# SCH_ZX-WiFi_2024-06-03.net
KiCad netlist of a schematic drawn in EasyEDA
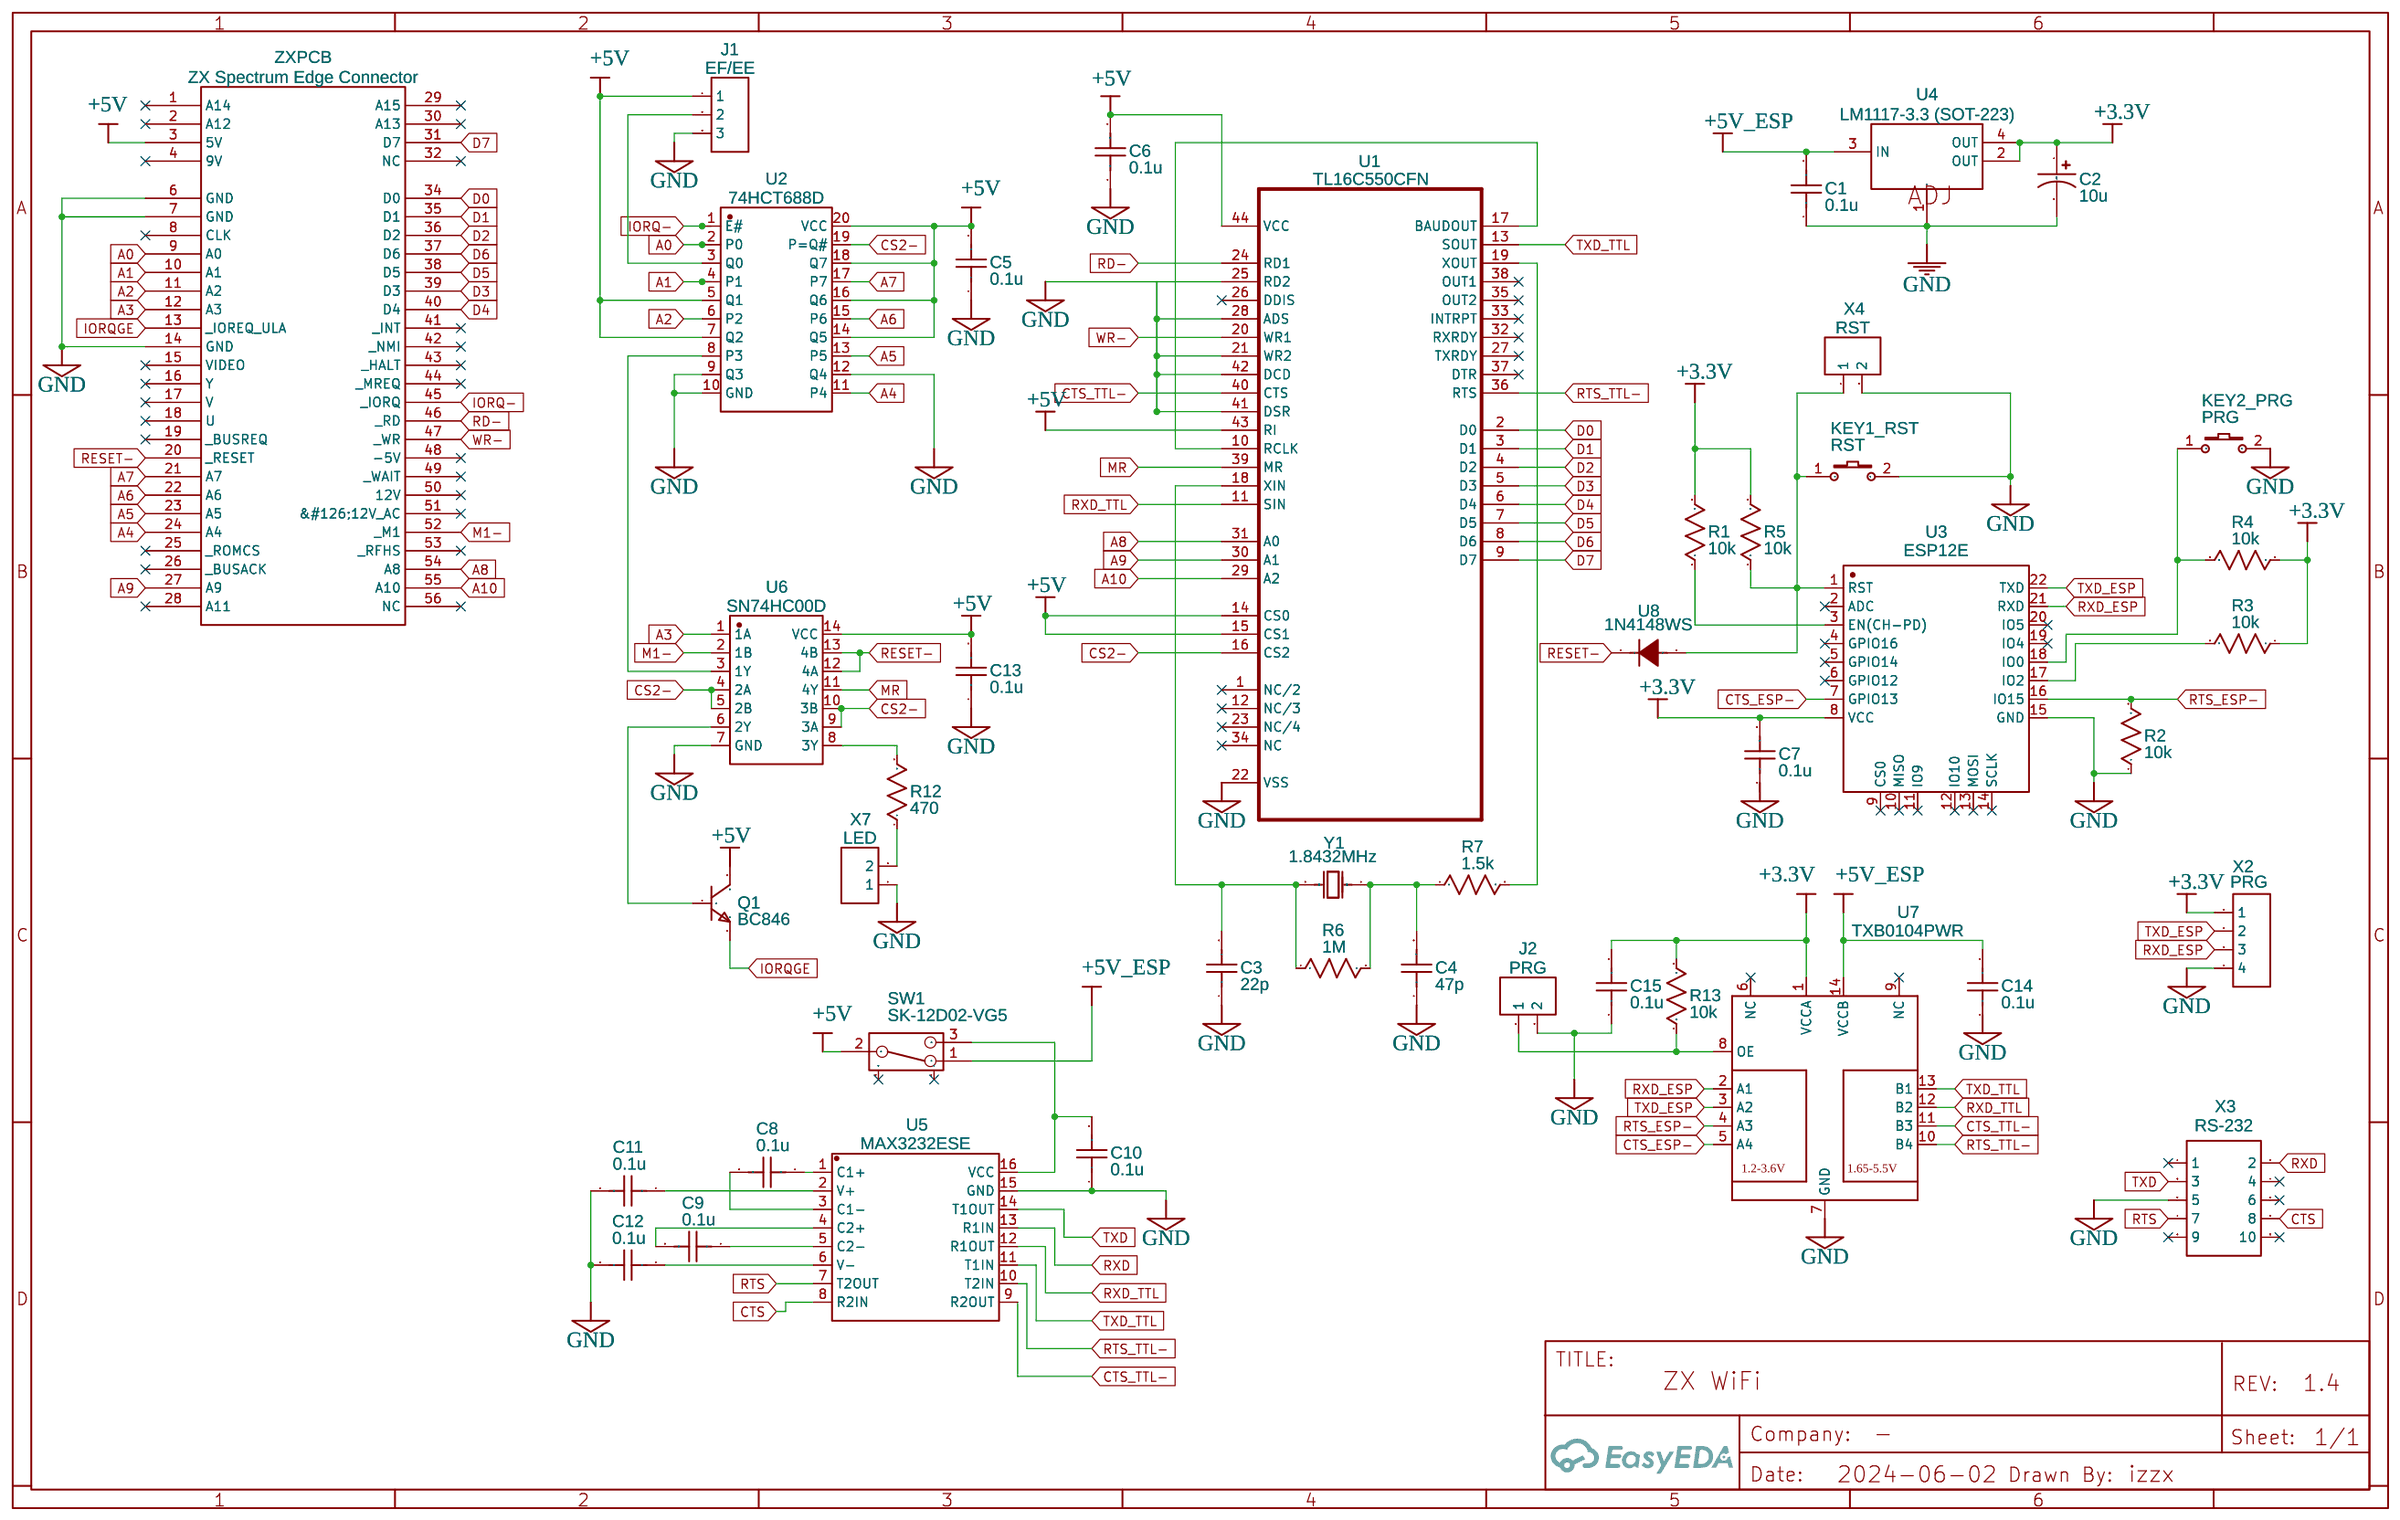
[diagram p0: schematic sheet]

(export (version "E")
  (design (tool "Eeschema 10.0.6"))
  (components
    (comp (ref "C1") (value "0.1u") (libsource (lib "") (part "C_0805_US_1")))
    (comp (ref "C2") (value "10u") (libsource (lib "") (part "C_Tan_SMD_A_US")))
    (comp (ref "C3") (value "22p") (libsource (lib "") (part "C_0805_US_1")))
    (comp (ref "C4") (value "47p") (libsource (lib "") (part "C_0805_US_1")))
    (comp (ref "C5") (value "0.1u") (libsource (lib "") (part "C_0805_US_1")))
    (comp (ref "C6") (value "0.1u") (libsource (lib "") (part "C_0805_US_1")))
    (comp (ref "C7") (value "0.1u") (libsource (lib "") (part "C_0805_US_1")))
    (comp (ref "C8") (value "0.1u") (libsource (lib "") (part "C_0805_US")))
    (comp (ref "C9") (value "0.1u") (libsource (lib "") (part "C_0805_US")))
    (comp (ref "C10") (value "0.1u") (libsource (lib "") (part "C_0805_US_1")))
    (comp (ref "C11") (value "0.1u") (libsource (lib "") (part "C_0805_US")))
    (comp (ref "C12") (value "0.1u") (libsource (lib "") (part "C_0805_US")))
    (comp (ref "C13") (value "0.1u") (libsource (lib "") (part "C_0805_US_1")))
    (comp (ref "C14") (value "0.1u") (libsource (lib "") (part "C_0805_US_1")))
    (comp (ref "C15") (value "0.1u") (libsource (lib "") (part "C_0805_US_1")))
    (comp (ref "J1") (value "EF/EE") (libsource (lib "") (part "HDR-M-2.54_1x3")))
    (comp (ref "J2") (value "PRG") (libsource (lib "") (part "HDR-M-2.54_1x2_2")))
    (comp (ref "KEY1_RST")
      (value "RST")
      (fields (field (name "Manufacturer Part") "K2-1107ST-A4SW-06"))
      (libsource (lib "") (part "K2-3.6×6.1_SMD"))
    )
    (comp (ref "KEY2_PRG")
      (value "PRG")
      (fields (field (name "Manufacturer Part") "K2-1107ST-A4SW-06"))
      (libsource (lib "") (part "K2-3.6×6.1_SMD_1"))
    )
    (comp (ref "Q1")
      (value "BC846")
      (fields (field (name "Manufacturer Part") "BC846A") (field (name "Manufacturer") "CJ(江苏长电/长晶)"))
      (libsource (lib "") (part "BC846"))
    )
    (comp (ref "R1") (value "10k") (libsource (lib "") (part "R_0805_US_2")))
    (comp (ref "R2") (value "10k") (libsource (lib "") (part "R_0805_US_2")))
    (comp (ref "R3") (value "10k") (libsource (lib "") (part "R_0805_US")))
    (comp (ref "R4") (value "10k") (libsource (lib "") (part "R_0805_US")))
    (comp (ref "R5") (value "10k") (libsource (lib "") (part "R_0805_US_2")))
    (comp (ref "R6") (value "1M") (libsource (lib "") (part "R_0805_US_1")))
    (comp (ref "R7") (value "1.5k") (libsource (lib "") (part "R_0805_US_1")))
    (comp (ref "R12") (value "470") (libsource (lib "") (part "R_0805_US_2")))
    (comp (ref "R13") (value "10k") (libsource (lib "") (part "R_0805_US_2")))
    (comp (ref "SW1")
      (value "SK-12D02-VG5")
      (fields (field (name "Manufacturer") "Rectangular Connectors - Contacts"))
      (libsource (lib "") (part "SK-12D02-VG5"))
    )
    (comp (ref "U1") (value "TL16C550CFN") (libsource (lib "") (part "TL16C550CFN")))
    (comp (ref "U2")
      (value "74HCT688D")
      (fields (field (name "Manufacturer") "PHILIPS"))
      (libsource (lib "") (part "74HCT688D"))
    )
    (comp (ref "U3") (value "ESP12E") (libsource (lib "") (part "ESP12E/F")))
    (comp (ref "U4")
      (value "LM1117-3.3 (SOT-223)")
      (fields (field (name "Manufacturer Part") "LM317G-AA3-R") (field (name "Manufacturer") "UTC"))
      (libsource (lib "") (part "LM317(SOT-223)"))
    )
    (comp (ref "U5")
      (value "MAX3232ESE")
      (fields (field (name "Manufacturer") "UMW(友台半导体)"))
      (libsource (lib "") (part "MAX3232ESE"))
    )
    (comp (ref "U6")
      (value "SN74HC00D")
      (fields (field (name "Manufacturer") "TI(德州仪器)"))
      (libsource (lib "") (part "SN74HC00D"))
    )
    (comp (ref "U7")
      (value "TXB0104PWR")
      (fields (field (name "Manufacturer") "TI(德州仪器)"))
      (libsource (lib "") (part "TXB0104PWR"))
    )
    (comp (ref "U8")
      (value "1N4148WS")
      (fields (field (name "Manufacturer") "Zhengxin(正芯)"))
      (libsource (lib "") (part "1N4148WS"))
    )
    (comp (ref "X2") (value "PRG") (libsource (lib "") (part "HDR-M-2.54_1x4")))
    (comp (ref "X3") (value "RS-232") (libsource (lib "") (part "HDR-M-2.54_2x5")))
    (comp (ref "X4") (value "RST") (libsource (lib "") (part "HDR-M-2.54_1x2_1")))
    (comp (ref "X7") (value "LED") (libsource (lib "") (part "HDR-M-2.54_1x2")))
    (comp (ref "Y1")
      (value "1.8432MHz")
      (fields (field (name "Manufacturer Part") "X49UD3579MSD2SC") (field (name "Manufacturer") "ValuePro"))
      (libsource (lib "") (part "X49UD3579MSD2SC"))
    )
    (comp (ref "ZXPCB")
      (value "ZX Spectrum Edge Connector")
      (libsource (lib "") (part "ZX Spectrum Edge Connector"))
    )
  )
  (nets
    (net (code "1") (name "+3.3V") (class "Default")
      (node (ref "C15") (pin "2") (pinfunction "2_2") (pintype "unspecified"))
      (node (ref "C2") (pin "1") (pinfunction "1_1") (pintype "unspecified"))
      (node (ref "C7") (pin "2") (pinfunction "2_2") (pintype "unspecified"))
      (node (ref "R1") (pin "2") (pinfunction "2_2") (pintype "unspecified"))
      (node (ref "R13") (pin "2") (pinfunction "2_2") (pintype "unspecified"))
      (node (ref "R3") (pin "1") (pinfunction "1_1") (pintype "unspecified"))
      (node (ref "R4") (pin "1") (pinfunction "1_1") (pintype "unspecified"))
      (node (ref "R5") (pin "2") (pinfunction "2_2") (pintype "unspecified"))
      (node (ref "U3") (pin "8") (pinfunction "VCC_8") (pintype "unspecified"))
      (node (ref "U4") (pin "2") (pinfunction "OUT_2") (pintype "passive"))
      (node (ref "U4") (pin "4") (pinfunction "OUT_4") (pintype "passive"))
      (node (ref "U7") (pin "1") (pinfunction "VCCA_1") (pintype "unspecified"))
      (node (ref "X2") (pin "1") (pinfunction "1_1") (pintype "unspecified"))
    )
    (net (code "2") (name "+5V") (class "Default")
      (node (ref "C13") (pin "2") (pinfunction "2_2") (pintype "unspecified"))
      (node (ref "C5") (pin "2") (pinfunction "2_2") (pintype "unspecified"))
      (node (ref "C6") (pin "2") (pinfunction "2_2") (pintype "unspecified"))
      (node (ref "J1") (pin "1") (pinfunction "1_1") (pintype "input"))
      (node (ref "Q1") (pin "3") (pinfunction "C_3") (pintype "unspecified"))
      (node (ref "SW1") (pin "2") (pinfunction "2_2") (pintype "unspecified"))
      (node (ref "U1") (pin "14") (pinfunction "CS0_14") (pintype "input"))
      (node (ref "U1") (pin "15") (pinfunction "CS1_15") (pintype "input"))
      (node (ref "U1") (pin "43") (pinfunction "RI_43") (pintype "input"))
      (node (ref "U1") (pin "44") (pinfunction "VCC_44") (pintype "passive"))
      (node (ref "U2") (pin "14") (pinfunction "Q5_14") (pintype "unspecified"))
      (node (ref "U2") (pin "16") (pinfunction "Q6_16") (pintype "unspecified"))
      (node (ref "U2") (pin "18") (pinfunction "Q7_18") (pintype "unspecified"))
      (node (ref "U2") (pin "20") (pinfunction "VCC_20") (pintype "unspecified"))
      (node (ref "U2") (pin "5") (pinfunction "Q1_5") (pintype "unspecified"))
      (node (ref "U2") (pin "7") (pinfunction "Q2_7") (pintype "unspecified"))
      (node (ref "U6") (pin "14") (pinfunction "VCC_14") (pintype "unspecified"))
      (node (ref "ZXPCB") (pin "3") (pinfunction "5V_3") (pintype "unspecified"))
    )
    (net (code "3") (name "+5V_ESP") (class "Default")
      (node (ref "C1") (pin "2") (pinfunction "2_2") (pintype "unspecified"))
      (node (ref "C14") (pin "2") (pinfunction "2_2") (pintype "unspecified"))
      (node (ref "SW1") (pin "1") (pinfunction "1_1") (pintype "unspecified"))
      (node (ref "U4") (pin "3") (pinfunction "IN_3") (pintype "passive"))
      (node (ref "U7") (pin "14") (pinfunction "VCCB_14") (pintype "unspecified"))
    )
    (net (code "4") (name "A0") (class "Default")
      (node (ref "U2") (pin "2") (pinfunction "P0_2") (pintype "unspecified"))
      (node (ref "ZXPCB") (pin "9") (pinfunction "A0_9") (pintype "unspecified"))
    )
    (net (code "5") (name "A1") (class "Default")
      (node (ref "U2") (pin "4") (pinfunction "P1_4") (pintype "unspecified"))
      (node (ref "ZXPCB") (pin "10") (pinfunction "A1_10") (pintype "unspecified"))
    )
    (net (code "6") (name "A2") (class "Default")
      (node (ref "U2") (pin "6") (pinfunction "P2_6") (pintype "unspecified"))
      (node (ref "ZXPCB") (pin "11") (pinfunction "A2_11") (pintype "unspecified"))
    )
    (net (code "7") (name "A3") (class "Default")
      (node (ref "U6") (pin "1") (pinfunction "1A_1") (pintype "unspecified"))
      (node (ref "ZXPCB") (pin "12") (pinfunction "A3_12") (pintype "unspecified"))
    )
    (net (code "8") (name "A4") (class "Default")
      (node (ref "U2") (pin "11") (pinfunction "P4_11") (pintype "unspecified"))
      (node (ref "ZXPCB") (pin "24") (pinfunction "A4_24") (pintype "unspecified"))
    )
    (net (code "9") (name "A5") (class "Default")
      (node (ref "U2") (pin "13") (pinfunction "P5_13") (pintype "unspecified"))
      (node (ref "ZXPCB") (pin "23") (pinfunction "A5_23") (pintype "unspecified"))
    )
    (net (code "10") (name "A6") (class "Default")
      (node (ref "U2") (pin "15") (pinfunction "P6_15") (pintype "unspecified"))
      (node (ref "ZXPCB") (pin "22") (pinfunction "A6_22") (pintype "unspecified"))
    )
    (net (code "11") (name "A7") (class "Default")
      (node (ref "U2") (pin "17") (pinfunction "P7_17") (pintype "unspecified"))
      (node (ref "ZXPCB") (pin "21") (pinfunction "A7_21") (pintype "unspecified"))
    )
    (net (code "12") (name "A8") (class "Default")
      (node (ref "U1") (pin "31") (pinfunction "A0_31") (pintype "input"))
      (node (ref "ZXPCB") (pin "54") (pinfunction "A8_54") (pintype "unspecified"))
    )
    (net (code "13") (name "A9") (class "Default")
      (node (ref "U1") (pin "30") (pinfunction "A1_30") (pintype "input"))
      (node (ref "ZXPCB") (pin "27") (pinfunction "A9_27") (pintype "unspecified"))
    )
    (net (code "14") (name "A10") (class "Default")
      (node (ref "U1") (pin "29") (pinfunction "A2_29") (pintype "input"))
      (node (ref "ZXPCB") (pin "55") (pinfunction "A10_55") (pintype "unspecified"))
    )
    (net (code "15") (name "CS2-") (class "Default")
      (node (ref "U1") (pin "16") (pinfunction "CS2_16") (pintype "input"))
      (node (ref "U2") (pin "19") (pinfunction "P=Q#_19") (pintype "unspecified"))
      (node (ref "U6") (pin "10") (pinfunction "3B_10") (pintype "unspecified"))
      (node (ref "U6") (pin "4") (pinfunction "2A_4") (pintype "unspecified"))
      (node (ref "U6") (pin "5") (pinfunction "2B_5") (pintype "unspecified"))
      (node (ref "U6") (pin "9") (pinfunction "3A_9") (pintype "unspecified"))
    )
    (net (code "16") (name "CTS") (class "Default")
      (node (ref "U5") (pin "8") (pinfunction "R2IN_8") (pintype "unspecified"))
      (node (ref "X3") (pin "8") (pinfunction "8_8") (pintype "unspecified"))
    )
    (net (code "17") (name "CTS_ESP-") (class "Default")
      (node (ref "U3") (pin "7") (pinfunction "GPIO13_7") (pintype "unspecified"))
      (node (ref "U7") (pin "5") (pinfunction "A4_5") (pintype "unspecified"))
    )
    (net (code "18") (name "CTS_TTL-") (class "Default")
      (node (ref "U1") (pin "40") (pinfunction "CTS_40") (pintype "input"))
      (node (ref "U5") (pin "9") (pinfunction "R2OUT_9") (pintype "unspecified"))
      (node (ref "U7") (pin "11") (pinfunction "B3_11") (pintype "unspecified"))
    )
    (net (code "19") (name "D0") (class "Default")
      (node (ref "U1") (pin "2") (pinfunction "D0_2") (pintype "unspecified"))
      (node (ref "ZXPCB") (pin "34") (pinfunction "D0_34") (pintype "unspecified"))
    )
    (net (code "20") (name "D1") (class "Default")
      (node (ref "U1") (pin "3") (pinfunction "D1_3") (pintype "unspecified"))
      (node (ref "ZXPCB") (pin "35") (pinfunction "D1_35") (pintype "unspecified"))
    )
    (net (code "21") (name "D2") (class "Default")
      (node (ref "U1") (pin "4") (pinfunction "D2_4") (pintype "unspecified"))
      (node (ref "ZXPCB") (pin "36") (pinfunction "D2_36") (pintype "unspecified"))
    )
    (net (code "22") (name "D3") (class "Default")
      (node (ref "U1") (pin "5") (pinfunction "D3_5") (pintype "unspecified"))
      (node (ref "ZXPCB") (pin "39") (pinfunction "D3_39") (pintype "unspecified"))
    )
    (net (code "23") (name "D4") (class "Default")
      (node (ref "U1") (pin "6") (pinfunction "D4_6") (pintype "unspecified"))
      (node (ref "ZXPCB") (pin "40") (pinfunction "D4_40") (pintype "unspecified"))
    )
    (net (code "24") (name "D5") (class "Default")
      (node (ref "U1") (pin "7") (pinfunction "D5_7") (pintype "unspecified"))
      (node (ref "ZXPCB") (pin "38") (pinfunction "D5_38") (pintype "unspecified"))
    )
    (net (code "25") (name "D6") (class "Default")
      (node (ref "U1") (pin "8") (pinfunction "D6_8") (pintype "unspecified"))
      (node (ref "ZXPCB") (pin "37") (pinfunction "D6_37") (pintype "unspecified"))
    )
    (net (code "26") (name "D7") (class "Default")
      (node (ref "U1") (pin "9") (pinfunction "D7_9") (pintype "unspecified"))
      (node (ref "ZXPCB") (pin "31") (pinfunction "D7_31") (pintype "unspecified"))
    )
    (net (code "27") (name "GND") (class "Default")
      (node (ref "C1") (pin "1") (pinfunction "1_1") (pintype "unspecified"))
      (node (ref "C10") (pin "1") (pinfunction "1_1") (pintype "unspecified"))
      (node (ref "C11") (pin "2") (pinfunction "2_2") (pintype "unspecified"))
      (node (ref "C12") (pin "2") (pinfunction "2_2") (pintype "unspecified"))
      (node (ref "C13") (pin "1") (pinfunction "1_1") (pintype "unspecified"))
      (node (ref "C14") (pin "1") (pinfunction "1_1") (pintype "unspecified"))
      (node (ref "C15") (pin "1") (pinfunction "1_1") (pintype "unspecified"))
      (node (ref "C2") (pin "2") (pinfunction "2_2") (pintype "unspecified"))
      (node (ref "C3") (pin "1") (pinfunction "1_1") (pintype "unspecified"))
      (node (ref "C4") (pin "1") (pinfunction "1_1") (pintype "unspecified"))
      (node (ref "C5") (pin "1") (pinfunction "1_1") (pintype "unspecified"))
      (node (ref "C6") (pin "1") (pinfunction "1_1") (pintype "unspecified"))
      (node (ref "C7") (pin "1") (pinfunction "1_1") (pintype "unspecified"))
      (node (ref "J1") (pin "3") (pinfunction "3_3") (pintype "input"))
      (node (ref "J2") (pin "2") (pinfunction "2_2") (pintype "unspecified"))
      (node (ref "KEY1_RST") (pin "2") (pinfunction "2_2") (pintype "unspecified"))
      (node (ref "KEY2_PRG") (pin "2") (pinfunction "2_2") (pintype "unspecified"))
      (node (ref "R2") (pin "1") (pinfunction "1_1") (pintype "unspecified"))
      (node (ref "U1") (pin "21") (pinfunction "WR2_21") (pintype "input"))
      (node (ref "U1") (pin "22") (pinfunction "VSS_22") (pintype "passive"))
      (node (ref "U1") (pin "25") (pinfunction "RD2_25") (pintype "input"))
      (node (ref "U1") (pin "28") (pinfunction "ADS_28") (pintype "input"))
      (node (ref "U1") (pin "41") (pinfunction "DSR_41") (pintype "input"))
      (node (ref "U1") (pin "42") (pinfunction "DCD_42") (pintype "input"))
      (node (ref "U2") (pin "10") (pinfunction "GND_10") (pintype "unspecified"))
      (node (ref "U2") (pin "12") (pinfunction "Q4_12") (pintype "unspecified"))
      (node (ref "U2") (pin "9") (pinfunction "Q3_9") (pintype "unspecified"))
      (node (ref "U3") (pin "15") (pinfunction "GND_15") (pintype "unspecified"))
      (node (ref "U4") (pin "1") (pinfunction "ADJ_1") (pintype "passive"))
      (node (ref "U5") (pin "15") (pinfunction "GND_15") (pintype "unspecified"))
      (node (ref "U6") (pin "7") (pinfunction "GND_7") (pintype "unspecified"))
      (node (ref "U7") (pin "7") (pinfunction "GND_7") (pintype "unspecified"))
      (node (ref "X2") (pin "4") (pinfunction "4_4") (pintype "unspecified"))
      (node (ref "X3") (pin "5") (pinfunction "5_5") (pintype "unspecified"))
      (node (ref "X4") (pin "2") (pinfunction "2_2") (pintype "unspecified"))
      (node (ref "X7") (pin "1") (pinfunction "1_1") (pintype "unspecified"))
      (node (ref "ZXPCB") (pin "14") (pinfunction "GND_14") (pintype "unspecified"))
      (node (ref "ZXPCB") (pin "6") (pinfunction "GND_6") (pintype "unspecified"))
      (node (ref "ZXPCB") (pin "7") (pinfunction "GND_7") (pintype "unspecified"))
    )
    (net (code "28") (name "IORQ-") (class "Default")
      (node (ref "U2") (pin "1") (pinfunction "E#_1") (pintype "unspecified"))
      (node (ref "ZXPCB") (pin "45") (pinfunction "_IORQ_45") (pintype "unspecified"))
    )
    (net (code "29") (name "IORQGE") (class "Default")
      (node (ref "Q1") (pin "2") (pinfunction "E_2") (pintype "unspecified"))
      (node (ref "ZXPCB") (pin "13") (pinfunction "_IOREQ_ULA_13") (pintype "unspecified"))
    )
    (net (code "30") (name "M1-") (class "Default")
      (node (ref "U6") (pin "2") (pinfunction "1B_2") (pintype "unspecified"))
      (node (ref "ZXPCB") (pin "52") (pinfunction "_M1_52") (pintype "unspecified"))
    )
    (net (code "31") (name "MR") (class "Default")
      (node (ref "U1") (pin "39") (pinfunction "MR_39") (pintype "input"))
      (node (ref "U6") (pin "11") (pinfunction "4Y_11") (pintype "unspecified"))
    )
    (net (code "32") (name "Net-(Q1-B)") (class "Default")
      (node (ref "Q1") (pin "1") (pinfunction "B_1") (pintype "unspecified"))
      (node (ref "U6") (pin "6") (pinfunction "2Y_6") (pintype "unspecified"))
    )
    (net (code "33") (name "Net-(R12-Pad1)") (class "Default")
      (node (ref "R12") (pin "1") (pinfunction "1_1") (pintype "unspecified"))
      (node (ref "X7") (pin "2") (pinfunction "2_2") (pintype "unspecified"))
    )
    (net (code "34") (name "Net-(U1-BAUDOUT)") (class "Default")
      (node (ref "U1") (pin "10") (pinfunction "RCLK_10") (pintype "input"))
      (node (ref "U1") (pin "17") (pinfunction "BAUDOUT_17") (pintype "output"))
    )
    (net (code "35") (name "Net-(U1-XIN)") (class "Default")
      (node (ref "C3") (pin "2") (pinfunction "2_2") (pintype "unspecified"))
      (node (ref "R6") (pin "1") (pinfunction "1_1") (pintype "unspecified"))
      (node (ref "U1") (pin "18") (pinfunction "XIN_18") (pintype "input"))
      (node (ref "Y1") (pin "2") (pinfunction "OSC2_2") (pintype "input"))
    )
    (net (code "36") (name "Net-(U1-XOUT)") (class "Default")
      (node (ref "R7") (pin "2") (pinfunction "2_2") (pintype "unspecified"))
      (node (ref "U1") (pin "19") (pinfunction "XOUT_19") (pintype "output"))
    )
    (net (code "37") (name "Net-(U2-P3)") (class "Default")
      (node (ref "U2") (pin "8") (pinfunction "P3_8") (pintype "unspecified"))
      (node (ref "U6") (pin "3") (pinfunction "1Y_3") (pintype "unspecified"))
    )
    (net (code "38") (name "Net-(U2-Q0)") (class "Default")
      (node (ref "J1") (pin "2") (pinfunction "2_2") (pintype "input"))
      (node (ref "U2") (pin "3") (pinfunction "Q0_3") (pintype "unspecified"))
    )
    (net (code "39") (name "Net-(U3-EN(CH-PD))") (class "Default")
      (node (ref "R1") (pin "1") (pinfunction "1_1") (pintype "unspecified"))
      (node (ref "U3") (pin "3") (pinfunction "EN(CH-PD)_3") (pintype "unspecified"))
    )
    (net (code "40") (name "Net-(U3-IO0)") (class "Default")
      (node (ref "KEY2_PRG") (pin "1") (pinfunction "1_1") (pintype "unspecified"))
      (node (ref "R4") (pin "2") (pinfunction "2_2") (pintype "unspecified"))
      (node (ref "U3") (pin "18") (pinfunction "IO0_18") (pintype "unspecified"))
    )
    (net (code "41") (name "Net-(U3-IO2)") (class "Default")
      (node (ref "R3") (pin "2") (pinfunction "2_2") (pintype "unspecified"))
      (node (ref "U3") (pin "17") (pinfunction "IO2_17") (pintype "unspecified"))
    )
    (net (code "42") (name "Net-(U3-RST)") (class "Default")
      (node (ref "KEY1_RST") (pin "1") (pinfunction "1_1") (pintype "unspecified"))
      (node (ref "R5") (pin "1") (pinfunction "1_1") (pintype "unspecified"))
      (node (ref "U3") (pin "1") (pinfunction "RST_1") (pintype "unspecified"))
      (node (ref "U8") (pin "2") (pinfunction "A_2") (pintype "unspecified"))
      (node (ref "X4") (pin "1") (pinfunction "1_1") (pintype "unspecified"))
    )
    (net (code "43") (name "Net-(U5-C1+)") (class "Default")
      (node (ref "C8") (pin "1") (pinfunction "1_1") (pintype "unspecified"))
      (node (ref "U5") (pin "1") (pinfunction "C1+_1") (pintype "unspecified"))
    )
    (net (code "44") (name "Net-(U5-C1-)") (class "Default")
      (node (ref "C8") (pin "2") (pinfunction "2_2") (pintype "unspecified"))
      (node (ref "U5") (pin "3") (pinfunction "C1-_3") (pintype "unspecified"))
    )
    (net (code "45") (name "Net-(U5-C2+)") (class "Default")
      (node (ref "C9") (pin "2") (pinfunction "2_2") (pintype "unspecified"))
      (node (ref "U5") (pin "4") (pinfunction "C2+_4") (pintype "unspecified"))
    )
    (net (code "46") (name "Net-(U5-C2-)") (class "Default")
      (node (ref "C9") (pin "1") (pinfunction "1_1") (pintype "unspecified"))
      (node (ref "U5") (pin "5") (pinfunction "C2-_5") (pintype "unspecified"))
    )
    (net (code "47") (name "Net-(U5-V+)") (class "Default")
      (node (ref "C11") (pin "1") (pinfunction "1_1") (pintype "unspecified"))
      (node (ref "U5") (pin "2") (pinfunction "V+_2") (pintype "unspecified"))
    )
    (net (code "48") (name "Net-(U5-V-)") (class "Default")
      (node (ref "C12") (pin "1") (pinfunction "1_1") (pintype "unspecified"))
      (node (ref "U5") (pin "6") (pinfunction "V-_6") (pintype "unspecified"))
    )
    (net (code "49") (name "Net-(U5-VCC)") (class "Default")
      (node (ref "C10") (pin "2") (pinfunction "2_2") (pintype "unspecified"))
      (node (ref "SW1") (pin "3") (pinfunction "3_3") (pintype "unspecified"))
      (node (ref "U5") (pin "16") (pinfunction "VCC_16") (pintype "unspecified"))
    )
    (net (code "50") (name "Net-(U6-3Y)") (class "Default")
      (node (ref "R12") (pin "2") (pinfunction "2_2") (pintype "unspecified"))
      (node (ref "U6") (pin "8") (pinfunction "3Y_8") (pintype "unspecified"))
    )
    (net (code "51") (name "Net-(U7-OE)") (class "Default")
      (node (ref "J2") (pin "1") (pinfunction "1_1") (pintype "unspecified"))
      (node (ref "R13") (pin "1") (pinfunction "1_1") (pintype "unspecified"))
      (node (ref "U7") (pin "8") (pinfunction "OE_8") (pintype "unspecified"))
    )
    (net (code "52") (name "Net-(Y1-OSC1)") (class "Default")
      (node (ref "C4") (pin "2") (pinfunction "2_2") (pintype "unspecified"))
      (node (ref "R6") (pin "2") (pinfunction "2_2") (pintype "unspecified"))
      (node (ref "R7") (pin "1") (pinfunction "1_1") (pintype "unspecified"))
      (node (ref "Y1") (pin "1") (pinfunction "OSC1_1") (pintype "input"))
    )
    (net (code "53") (name "RD-") (class "Default")
      (node (ref "U1") (pin "24") (pinfunction "RD1_24") (pintype "input"))
      (node (ref "ZXPCB") (pin "46") (pinfunction "_RD_46") (pintype "unspecified"))
    )
    (net (code "54") (name "RESET-") (class "Default")
      (node (ref "U6") (pin "12") (pinfunction "4A_12") (pintype "unspecified"))
      (node (ref "U6") (pin "13") (pinfunction "4B_13") (pintype "unspecified"))
      (node (ref "U8") (pin "1") (pinfunction "K_1") (pintype "unspecified"))
      (node (ref "ZXPCB") (pin "20") (pinfunction "_RESET_20") (pintype "unspecified"))
    )
    (net (code "55") (name "RTS") (class "Default")
      (node (ref "U5") (pin "7") (pinfunction "T2OUT_7") (pintype "unspecified"))
      (node (ref "X3") (pin "7") (pinfunction "7_7") (pintype "unspecified"))
    )
    (net (code "56") (name "RTS_ESP-") (class "Default")
      (node (ref "R2") (pin "2") (pinfunction "2_2") (pintype "unspecified"))
      (node (ref "U3") (pin "16") (pinfunction "IO15_16") (pintype "unspecified"))
      (node (ref "U7") (pin "4") (pinfunction "A3_4") (pintype "unspecified"))
    )
    (net (code "57") (name "RTS_TTL-") (class "Default")
      (node (ref "U1") (pin "36") (pinfunction "RTS_36") (pintype "output"))
      (node (ref "U5") (pin "10") (pinfunction "T2IN_10") (pintype "unspecified"))
      (node (ref "U7") (pin "10") (pinfunction "B4_10") (pintype "unspecified"))
    )
    (net (code "58") (name "RXD") (class "Default")
      (node (ref "U5") (pin "13") (pinfunction "R1IN_13") (pintype "unspecified"))
      (node (ref "X3") (pin "2") (pinfunction "2_2") (pintype "unspecified"))
    )
    (net (code "59") (name "RXD_ESP") (class "Default")
      (node (ref "U3") (pin "21") (pinfunction "RXD_21") (pintype "unspecified"))
      (node (ref "U7") (pin "2") (pinfunction "A1_2") (pintype "unspecified"))
      (node (ref "X2") (pin "3") (pinfunction "3_3") (pintype "unspecified"))
    )
    (net (code "60") (name "RXD_TTL") (class "Default")
      (node (ref "U1") (pin "11") (pinfunction "SIN_11") (pintype "input"))
      (node (ref "U5") (pin "12") (pinfunction "R1OUT_12") (pintype "unspecified"))
      (node (ref "U7") (pin "12") (pinfunction "B2_12") (pintype "unspecified"))
    )
    (net (code "61") (name "TXD") (class "Default")
      (node (ref "U5") (pin "14") (pinfunction "T1OUT_14") (pintype "unspecified"))
      (node (ref "X3") (pin "3") (pinfunction "3_3") (pintype "unspecified"))
    )
    (net (code "62") (name "TXD_ESP") (class "Default")
      (node (ref "U3") (pin "22") (pinfunction "TXD_22") (pintype "unspecified"))
      (node (ref "U7") (pin "3") (pinfunction "A2_3") (pintype "unspecified"))
      (node (ref "X2") (pin "2") (pinfunction "2_2") (pintype "unspecified"))
    )
    (net (code "63") (name "TXD_TTL") (class "Default")
      (node (ref "U1") (pin "13") (pinfunction "SOUT_13") (pintype "output"))
      (node (ref "U5") (pin "11") (pinfunction "T1IN_11") (pintype "unspecified"))
      (node (ref "U7") (pin "13") (pinfunction "B1_13") (pintype "unspecified"))
    )
    (net (code "64") (name "WR-") (class "Default")
      (node (ref "U1") (pin "20") (pinfunction "WR1_20") (pintype "input"))
      (node (ref "ZXPCB") (pin "47") (pinfunction "_WR_47") (pintype "unspecified"))
    )
    (net (code "65") (name "unconnected-(SW1-Pad4)") (class "Default")
      (node (ref "SW1") (pin "4") (pinfunction "4_4") (pintype "unspecified+no_connect"))
    )
    (net (code "66") (name "unconnected-(SW1-Pad5)") (class "Default")
      (node (ref "SW1") (pin "5") (pinfunction "5_5") (pintype "unspecified+no_connect"))
    )
    (net (code "67") (name "unconnected-(U1-DDIS-Pad26)") (class "Default")
      (node (ref "U1") (pin "26") (pinfunction "DDIS_26") (pintype "input+no_connect"))
    )
    (net (code "68") (name "unconnected-(U1-DTR-Pad37)") (class "Default")
      (node (ref "U1") (pin "37") (pinfunction "DTR_37") (pintype "output+no_connect"))
    )
    (net (code "69") (name "unconnected-(U1-INTRPT-Pad33)") (class "Default")
      (node (ref "U1") (pin "33") (pinfunction "INTRPT_33") (pintype "output+no_connect"))
    )
    (net (code "70") (name "unconnected-(U1-NC-Pad34)") (class "Default")
      (node (ref "U1") (pin "34") (pinfunction "NC_34") (pintype "unspecified+no_connect"))
    )
    (net (code "71") (name "unconnected-(U1-NC{slash}2-Pad1)") (class "Default")
      (node (ref "U1") (pin "1") (pinfunction "NC/2_1") (pintype "unspecified+no_connect"))
    )
    (net (code "72") (name "unconnected-(U1-NC{slash}3-Pad12)") (class "Default")
      (node (ref "U1") (pin "12") (pinfunction "NC/3_12") (pintype "unspecified+no_connect"))
    )
    (net (code "73") (name "unconnected-(U1-NC{slash}4-Pad23)") (class "Default")
      (node (ref "U1") (pin "23") (pinfunction "NC/4_23") (pintype "unspecified+no_connect"))
    )
    (net (code "74") (name "unconnected-(U1-OUT1-Pad38)") (class "Default")
      (node (ref "U1") (pin "38") (pinfunction "OUT1_38") (pintype "output+no_connect"))
    )
    (net (code "75") (name "unconnected-(U1-OUT2-Pad35)") (class "Default")
      (node (ref "U1") (pin "35") (pinfunction "OUT2_35") (pintype "output+no_connect"))
    )
    (net (code "76") (name "unconnected-(U1-RXRDY-Pad32)") (class "Default")
      (node (ref "U1") (pin "32") (pinfunction "RXRDY_32") (pintype "output+no_connect"))
    )
    (net (code "77") (name "unconnected-(U1-TXRDY-Pad27)") (class "Default")
      (node (ref "U1") (pin "27") (pinfunction "TXRDY_27") (pintype "output+no_connect"))
    )
    (net (code "78") (name "unconnected-(U3-ADC-Pad2)") (class "Default")
      (node (ref "U3") (pin "2") (pinfunction "ADC_2") (pintype "unspecified+no_connect"))
    )
    (net (code "79") (name "unconnected-(U3-CS0-Pad9)") (class "Default")
      (node (ref "U3") (pin "9") (pinfunction "CS0_9") (pintype "unspecified+no_connect"))
    )
    (net (code "80") (name "unconnected-(U3-GPIO12-Pad6)") (class "Default")
      (node (ref "U3") (pin "6") (pinfunction "GPIO12_6") (pintype "unspecified+no_connect"))
    )
    (net (code "81") (name "unconnected-(U3-GPIO14-Pad5)") (class "Default")
      (node (ref "U3") (pin "5") (pinfunction "GPIO14_5") (pintype "unspecified+no_connect"))
    )
    (net (code "82") (name "unconnected-(U3-GPIO16-Pad4)") (class "Default")
      (node (ref "U3") (pin "4") (pinfunction "GPIO16_4") (pintype "unspecified+no_connect"))
    )
    (net (code "83") (name "unconnected-(U3-IO4-Pad19)") (class "Default")
      (node (ref "U3") (pin "19") (pinfunction "IO4_19") (pintype "unspecified+no_connect"))
    )
    (net (code "84") (name "unconnected-(U3-IO5-Pad20)") (class "Default")
      (node (ref "U3") (pin "20") (pinfunction "IO5_20") (pintype "unspecified+no_connect"))
    )
    (net (code "85") (name "unconnected-(U3-IO9-Pad11)") (class "Default")
      (node (ref "U3") (pin "11") (pinfunction "IO9_11") (pintype "unspecified+no_connect"))
    )
    (net (code "86") (name "unconnected-(U3-IO10-Pad12)") (class "Default")
      (node (ref "U3") (pin "12") (pinfunction "IO10_12") (pintype "unspecified+no_connect"))
    )
    (net (code "87") (name "unconnected-(U3-MISO-Pad10)") (class "Default")
      (node (ref "U3") (pin "10") (pinfunction "MISO_10") (pintype "unspecified+no_connect"))
    )
    (net (code "88") (name "unconnected-(U3-MOSI-Pad13)") (class "Default")
      (node (ref "U3") (pin "13") (pinfunction "MOSI_13") (pintype "unspecified+no_connect"))
    )
    (net (code "89") (name "unconnected-(U3-SCLK-Pad14)") (class "Default")
      (node (ref "U3") (pin "14") (pinfunction "SCLK_14") (pintype "unspecified+no_connect"))
    )
    (net (code "90") (name "unconnected-(U7-NC-Pad6)") (class "Default")
      (node (ref "U7") (pin "6") (pinfunction "NC_6") (pintype "unspecified+no_connect"))
    )
    (net (code "91") (name "unconnected-(U7-NC-Pad9)") (class "Default")
      (node (ref "U7") (pin "9") (pinfunction "NC_9") (pintype "unspecified+no_connect"))
    )
    (net (code "92") (name "unconnected-(X3-Pad1)") (class "Default")
      (node (ref "X3") (pin "1") (pinfunction "1_1") (pintype "unspecified+no_connect"))
    )
    (net (code "93") (name "unconnected-(X3-Pad4)") (class "Default")
      (node (ref "X3") (pin "4") (pinfunction "4_4") (pintype "unspecified+no_connect"))
    )
    (net (code "94") (name "unconnected-(X3-Pad6)") (class "Default")
      (node (ref "X3") (pin "6") (pinfunction "6_6") (pintype "unspecified+no_connect"))
    )
    (net (code "95") (name "unconnected-(X3-Pad9)") (class "Default")
      (node (ref "X3") (pin "9") (pinfunction "9_9") (pintype "unspecified+no_connect"))
    )
    (net (code "96") (name "unconnected-(X3-Pad10)") (class "Default")
      (node (ref "X3") (pin "10") (pinfunction "10_10") (pintype "unspecified+no_connect"))
    )
    (net (code "97") (name "unconnected-(ZXPCB-&#126;12V_AC-Pad51)") (class "Default")
      (node (ref "ZXPCB") (pin "51") (pinfunction "&#126;12V_AC_51") (pintype "unspecified+no_connect"))
    )
    (net (code "98") (name "unconnected-(ZXPCB--5V-Pad48)") (class "Default")
      (node (ref "ZXPCB") (pin "48") (pinfunction "-5V_48") (pintype "unspecified+no_connect"))
    )
    (net (code "99") (name "unconnected-(ZXPCB-9V-Pad4)") (class "Default")
      (node (ref "ZXPCB") (pin "4") (pinfunction "9V_4") (pintype "unspecified+no_connect"))
    )
    (net (code "100") (name "unconnected-(ZXPCB-12V-Pad50)") (class "Default")
      (node (ref "ZXPCB") (pin "50") (pinfunction "12V_50") (pintype "unspecified+no_connect"))
    )
    (net (code "101") (name "unconnected-(ZXPCB-A11-Pad28)") (class "Default")
      (node (ref "ZXPCB") (pin "28") (pinfunction "A11_28") (pintype "unspecified+no_connect"))
    )
    (net (code "102") (name "unconnected-(ZXPCB-A12-Pad2)") (class "Default")
      (node (ref "ZXPCB") (pin "2") (pinfunction "A12_2") (pintype "unspecified+no_connect"))
    )
    (net (code "103") (name "unconnected-(ZXPCB-A13-Pad30)") (class "Default")
      (node (ref "ZXPCB") (pin "30") (pinfunction "A13_30") (pintype "unspecified+no_connect"))
    )
    (net (code "104") (name "unconnected-(ZXPCB-A14-Pad1)") (class "Default")
      (node (ref "ZXPCB") (pin "1") (pinfunction "A14_1") (pintype "unspecified+no_connect"))
    )
    (net (code "105") (name "unconnected-(ZXPCB-A15-Pad29)") (class "Default")
      (node (ref "ZXPCB") (pin "29") (pinfunction "A15_29") (pintype "unspecified+no_connect"))
    )
    (net (code "106") (name "unconnected-(ZXPCB-CLK-Pad8)") (class "Default")
      (node (ref "ZXPCB") (pin "8") (pinfunction "CLK_8") (pintype "unspecified+no_connect"))
    )
    (net (code "107") (name "unconnected-(ZXPCB-NC-Pad32)") (class "Default")
      (node (ref "ZXPCB") (pin "32") (pinfunction "NC_32") (pintype "unspecified+no_connect"))
    )
    (net (code "108") (name "unconnected-(ZXPCB-NC-Pad56)") (class "Default")
      (node (ref "ZXPCB") (pin "56") (pinfunction "NC_56") (pintype "unspecified+no_connect"))
    )
    (net (code "109") (name "unconnected-(ZXPCB-U-Pad18)") (class "Default")
      (node (ref "ZXPCB") (pin "18") (pinfunction "U_18") (pintype "unspecified+no_connect"))
    )
    (net (code "110") (name "unconnected-(ZXPCB-V-Pad17)") (class "Default")
      (node (ref "ZXPCB") (pin "17") (pinfunction "V_17") (pintype "unspecified+no_connect"))
    )
    (net (code "111") (name "unconnected-(ZXPCB-VIDEO-Pad15)") (class "Default")
      (node (ref "ZXPCB") (pin "15") (pinfunction "VIDEO_15") (pintype "unspecified+no_connect"))
    )
    (net (code "112") (name "unconnected-(ZXPCB-Y-Pad16)") (class "Default")
      (node (ref "ZXPCB") (pin "16") (pinfunction "Y_16") (pintype "unspecified+no_connect"))
    )
    (net (code "113") (name "unconnected-(ZXPCB-_BUSACK-Pad26)") (class "Default")
      (node (ref "ZXPCB") (pin "26") (pinfunction "_BUSACK_26") (pintype "unspecified+no_connect"))
    )
    (net (code "114") (name "unconnected-(ZXPCB-_BUSREQ-Pad19)") (class "Default")
      (node (ref "ZXPCB") (pin "19") (pinfunction "_BUSREQ_19") (pintype "unspecified+no_connect"))
    )
    (net (code "115") (name "unconnected-(ZXPCB-_HALT-Pad43)") (class "Default")
      (node (ref "ZXPCB") (pin "43") (pinfunction "_HALT_43") (pintype "unspecified+no_connect"))
    )
    (net (code "116") (name "unconnected-(ZXPCB-_INT-Pad41)") (class "Default")
      (node (ref "ZXPCB") (pin "41") (pinfunction "_INT_41") (pintype "unspecified+no_connect"))
    )
    (net (code "117") (name "unconnected-(ZXPCB-_MREQ-Pad44)") (class "Default")
      (node (ref "ZXPCB") (pin "44") (pinfunction "_MREQ_44") (pintype "unspecified+no_connect"))
    )
    (net (code "118") (name "unconnected-(ZXPCB-_NMI-Pad42)") (class "Default")
      (node (ref "ZXPCB") (pin "42") (pinfunction "_NMI_42") (pintype "unspecified+no_connect"))
    )
    (net (code "119") (name "unconnected-(ZXPCB-_RFHS-Pad53)") (class "Default")
      (node (ref "ZXPCB") (pin "53") (pinfunction "_RFHS_53") (pintype "unspecified+no_connect"))
    )
    (net (code "120") (name "unconnected-(ZXPCB-_ROMCS-Pad25)") (class "Default")
      (node (ref "ZXPCB") (pin "25") (pinfunction "_ROMCS_25") (pintype "unspecified+no_connect"))
    )
    (net (code "121") (name "unconnected-(ZXPCB-_WAIT-Pad49)") (class "Default")
      (node (ref "ZXPCB") (pin "49") (pinfunction "_WAIT_49") (pintype "unspecified+no_connect"))
    )
  )
)
